# relay_switch_fet.net
KiCad netlist of a schematic drawn in EAGLE
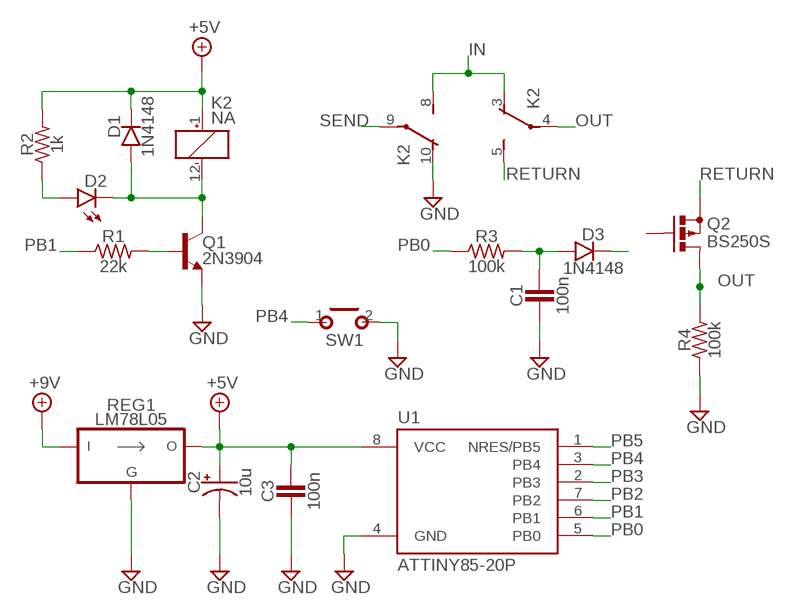
[diagram p0: schematic, sheet 1]

(export (version "E")
  (design (tool "Eeschema 10.0.6"))
  (components
    (comp (ref "C1")
      (value "100n")
      (footprint "eagle-import:BOX_SMALL")
      (libsource (lib "eagle-import") (part "CER/FILMBOX.1"))
    )
    (comp (ref "C2")
      (value "10u")
      (footprint "eagle-import:050_020")
      (libsource (lib "eagle-import") (part "0500"))
    )
    (comp (ref "C3")
      (value "100n")
      (footprint "eagle-import:050X030_025_2")
      (libsource (lib "eagle-import") (part "CER/FILM2"))
    )
    (comp (ref "D1")
      (value "1N4148")
      (footprint "eagle-import:DO35-2")
      (libsource (lib "eagle-import") (part "DO35.2"))
    )
    (comp (ref "D2")
      (value "LED")
      (footprint "eagle-import:3MM_D")
      (libsource (lib "eagle-import") (part "LED"))
    )
    (comp (ref "D3")
      (value "1N4148")
      (footprint "eagle-import:DO35-2")
      (libsource (lib "eagle-import") (part "DO35.2"))
    )
    (comp (ref "K2") (value "NA") (footprint "eagle-import:NA") (libsource (lib "eagle-import") (part "NA")))
    (comp (ref "Q1")
      (value "2N3904")
      (footprint "eagle-import:TO92-")
      (libsource (lib "eagle-import") (part "2N3904"))
    )
    (comp (ref "Q2")
      (value "BS250S")
      (footprint "eagle-import:SOT54ES")
      (libsource (lib "eagle-import") (part "BS250S"))
    )
    (comp (ref "R1")
      (value "22k")
      (footprint "eagle-import:R0207_3")
      (libsource (lib "eagle-import") (part "R_.3B"))
    )
    (comp (ref "R2")
      (value "1k")
      (footprint "eagle-import:R0207_3")
      (libsource (lib "eagle-import") (part "R_.3B"))
    )
    (comp (ref "R3")
      (value "100k")
      (footprint "eagle-import:R0207_3")
      (libsource (lib "eagle-import") (part "R_.3B"))
    )
    (comp (ref "R4")
      (value "100k")
      (footprint "eagle-import:R0207_3")
      (libsource (lib "eagle-import") (part "R_.3B"))
    )
    (comp (ref "REG1")
      (value "LM78L05")
      (footprint "eagle-import:TO92-")
      (libsource (lib "eagle-import") (part "LM78L05"))
    )
    (comp (ref "SW1")
      (value "MOMENTARY")
      (footprint "eagle-import:SPST")
      (libsource (lib "eagle-import") (part "MOMENTARY"))
    )
    (comp (ref "U1")
      (value "ATTINY85-20P")
      (footprint "eagle-import:PDIP08_300MIL")
      (libsource (lib "eagle-import") (part "ATTINY85P-20"))
    )
  )
  (nets
    (net (code "1") (name "+5V") (class "Default")
      (node (ref "C2") (pin "+") (pinfunction "+_+") (pintype "passive"))
      (node (ref "C3") (pin "1") (pinfunction "1_1") (pintype "passive"))
      (node (ref "D1") (pin "C") (pinfunction "C_C") (pintype "passive"))
      (node (ref "K2") (pin "1") (pinfunction "+_1") (pintype "passive"))
      (node (ref "R2") (pin "2") (pinfunction "2_2") (pintype "passive"))
      (node (ref "REG1") (pin "3") (pinfunction "VO_3") (pintype "passive"))
      (node (ref "U1") (pin "8") (pinfunction "VCC_8") (pintype "power_in"))
    )
    (net (code "2") (name "+9V") (class "Default")
      (node (ref "REG1") (pin "1") (pinfunction "VI_1") (pintype "input"))
    )
    (net (code "3") (name "/IN") (class "Default")
      (node (ref "K2") (pin "3") (pinfunction "O_3") (pintype "passive"))
      (node (ref "K2") (pin "8") (pinfunction "S_8") (pintype "passive"))
    )
    (net (code "4") (name "/OUT") (class "Default")
      (node (ref "K2") (pin "4") (pinfunction "P_4") (pintype "passive"))
      (node (ref "Q2") (pin "D") (pinfunction "D_D") (pintype "passive"))
      (node (ref "R4") (pin "2") (pinfunction "2_2") (pintype "passive"))
    )
    (net (code "5") (name "/PB0") (class "Default")
      (node (ref "R3") (pin "1") (pinfunction "1_1") (pintype "passive"))
      (node (ref "U1") (pin "5") (pinfunction "PB0_5") (pintype "bidirectional"))
    )
    (net (code "6") (name "/PB1") (class "Default")
      (node (ref "R1") (pin "1") (pinfunction "1_1") (pintype "passive"))
      (node (ref "U1") (pin "6") (pinfunction "PB1_6") (pintype "bidirectional"))
    )
    (net (code "7") (name "/PB2") (class "Default")
      (node (ref "U1") (pin "7") (pinfunction "PB2_7") (pintype "bidirectional"))
    )
    (net (code "8") (name "/PB3") (class "Default")
      (node (ref "U1") (pin "2") (pinfunction "PB3_2") (pintype "bidirectional"))
    )
    (net (code "9") (name "/PB4") (class "Default")
      (node (ref "SW1") (pin "1") (pinfunction "P_1") (pintype "passive"))
      (node (ref "U1") (pin "3") (pinfunction "PB4_3") (pintype "bidirectional"))
    )
    (net (code "10") (name "/PB5") (class "Default")
      (node (ref "U1") (pin "1") (pinfunction "NRES/PB5_1") (pintype "bidirectional"))
    )
    (net (code "11") (name "/RETURN") (class "Default")
      (node (ref "K2") (pin "5") (pinfunction "S_5") (pintype "passive"))
      (node (ref "Q2") (pin "S") (pinfunction "S_S") (pintype "passive"))
    )
    (net (code "12") (name "/SEND") (class "Default")
      (node (ref "K2") (pin "9") (pinfunction "P_9") (pintype "passive"))
    )
    (net (code "13") (name "GND") (class "Default")
      (node (ref "C1") (pin "2") (pinfunction "2_2") (pintype "passive"))
      (node (ref "C2") (pin "-") (pinfunction "-_-") (pintype "passive"))
      (node (ref "C3") (pin "2") (pinfunction "2_2") (pintype "passive"))
      (node (ref "K2") (pin "10") (pinfunction "O_10") (pintype "passive"))
      (node (ref "Q1") (pin "3") (pinfunction "E_3") (pintype "passive"))
      (node (ref "R4") (pin "1") (pinfunction "1_1") (pintype "passive"))
      (node (ref "REG1") (pin "2") (pinfunction "GND_2") (pintype "passive"))
      (node (ref "SW1") (pin "2") (pinfunction "S_2") (pintype "passive"))
      (node (ref "U1") (pin "4") (pinfunction "GND_4") (pintype "power_in"))
    )
    (net (code "14") (name "Net-(C1-Pad1)") (class "Default")
      (node (ref "C1") (pin "1") (pinfunction "1_1") (pintype "passive"))
      (node (ref "D3") (pin "A") (pinfunction "A_A") (pintype "passive"))
      (node (ref "R3") (pin "2") (pinfunction "2_2") (pintype "passive"))
    )
    (net (code "15") (name "Net-(D2-A)") (class "Default")
      (node (ref "D2") (pin "ANODE") (pinfunction "A_ANODE") (pintype "passive"))
      (node (ref "R2") (pin "1") (pinfunction "1_1") (pintype "passive"))
    )
    (net (code "16") (name "Net-(D2-C)") (class "Default")
      (node (ref "D1") (pin "A") (pinfunction "A_A") (pintype "passive"))
      (node (ref "D2") (pin "P$1") (pinfunction "C_P$1") (pintype "passive"))
      (node (ref "K2") (pin "12") (pinfunction "-_12") (pintype "passive"))
      (node (ref "Q1") (pin "1") (pinfunction "C_1") (pintype "passive"))
    )
    (net (code "17") (name "Net-(Q1-B)") (class "Default")
      (node (ref "Q1") (pin "2") (pinfunction "B_2") (pintype "passive"))
      (node (ref "R1") (pin "2") (pinfunction "2_2") (pintype "passive"))
    )
    (net (code "18") (name "unconnected-(D3-PadC)") (class "Default")
      (node (ref "D3") (pin "C") (pinfunction "C_C") (pintype "passive"))
    )
    (net (code "19") (name "unconnected-(Q2-PadG)") (class "Default")
      (node (ref "Q2") (pin "G") (pinfunction "G_G") (pintype "passive"))
    )
  )
)
